# PGTN_daisy1_main_8cvin_2cvout.net
KiCad netlist of a schematic drawn in EAGLE
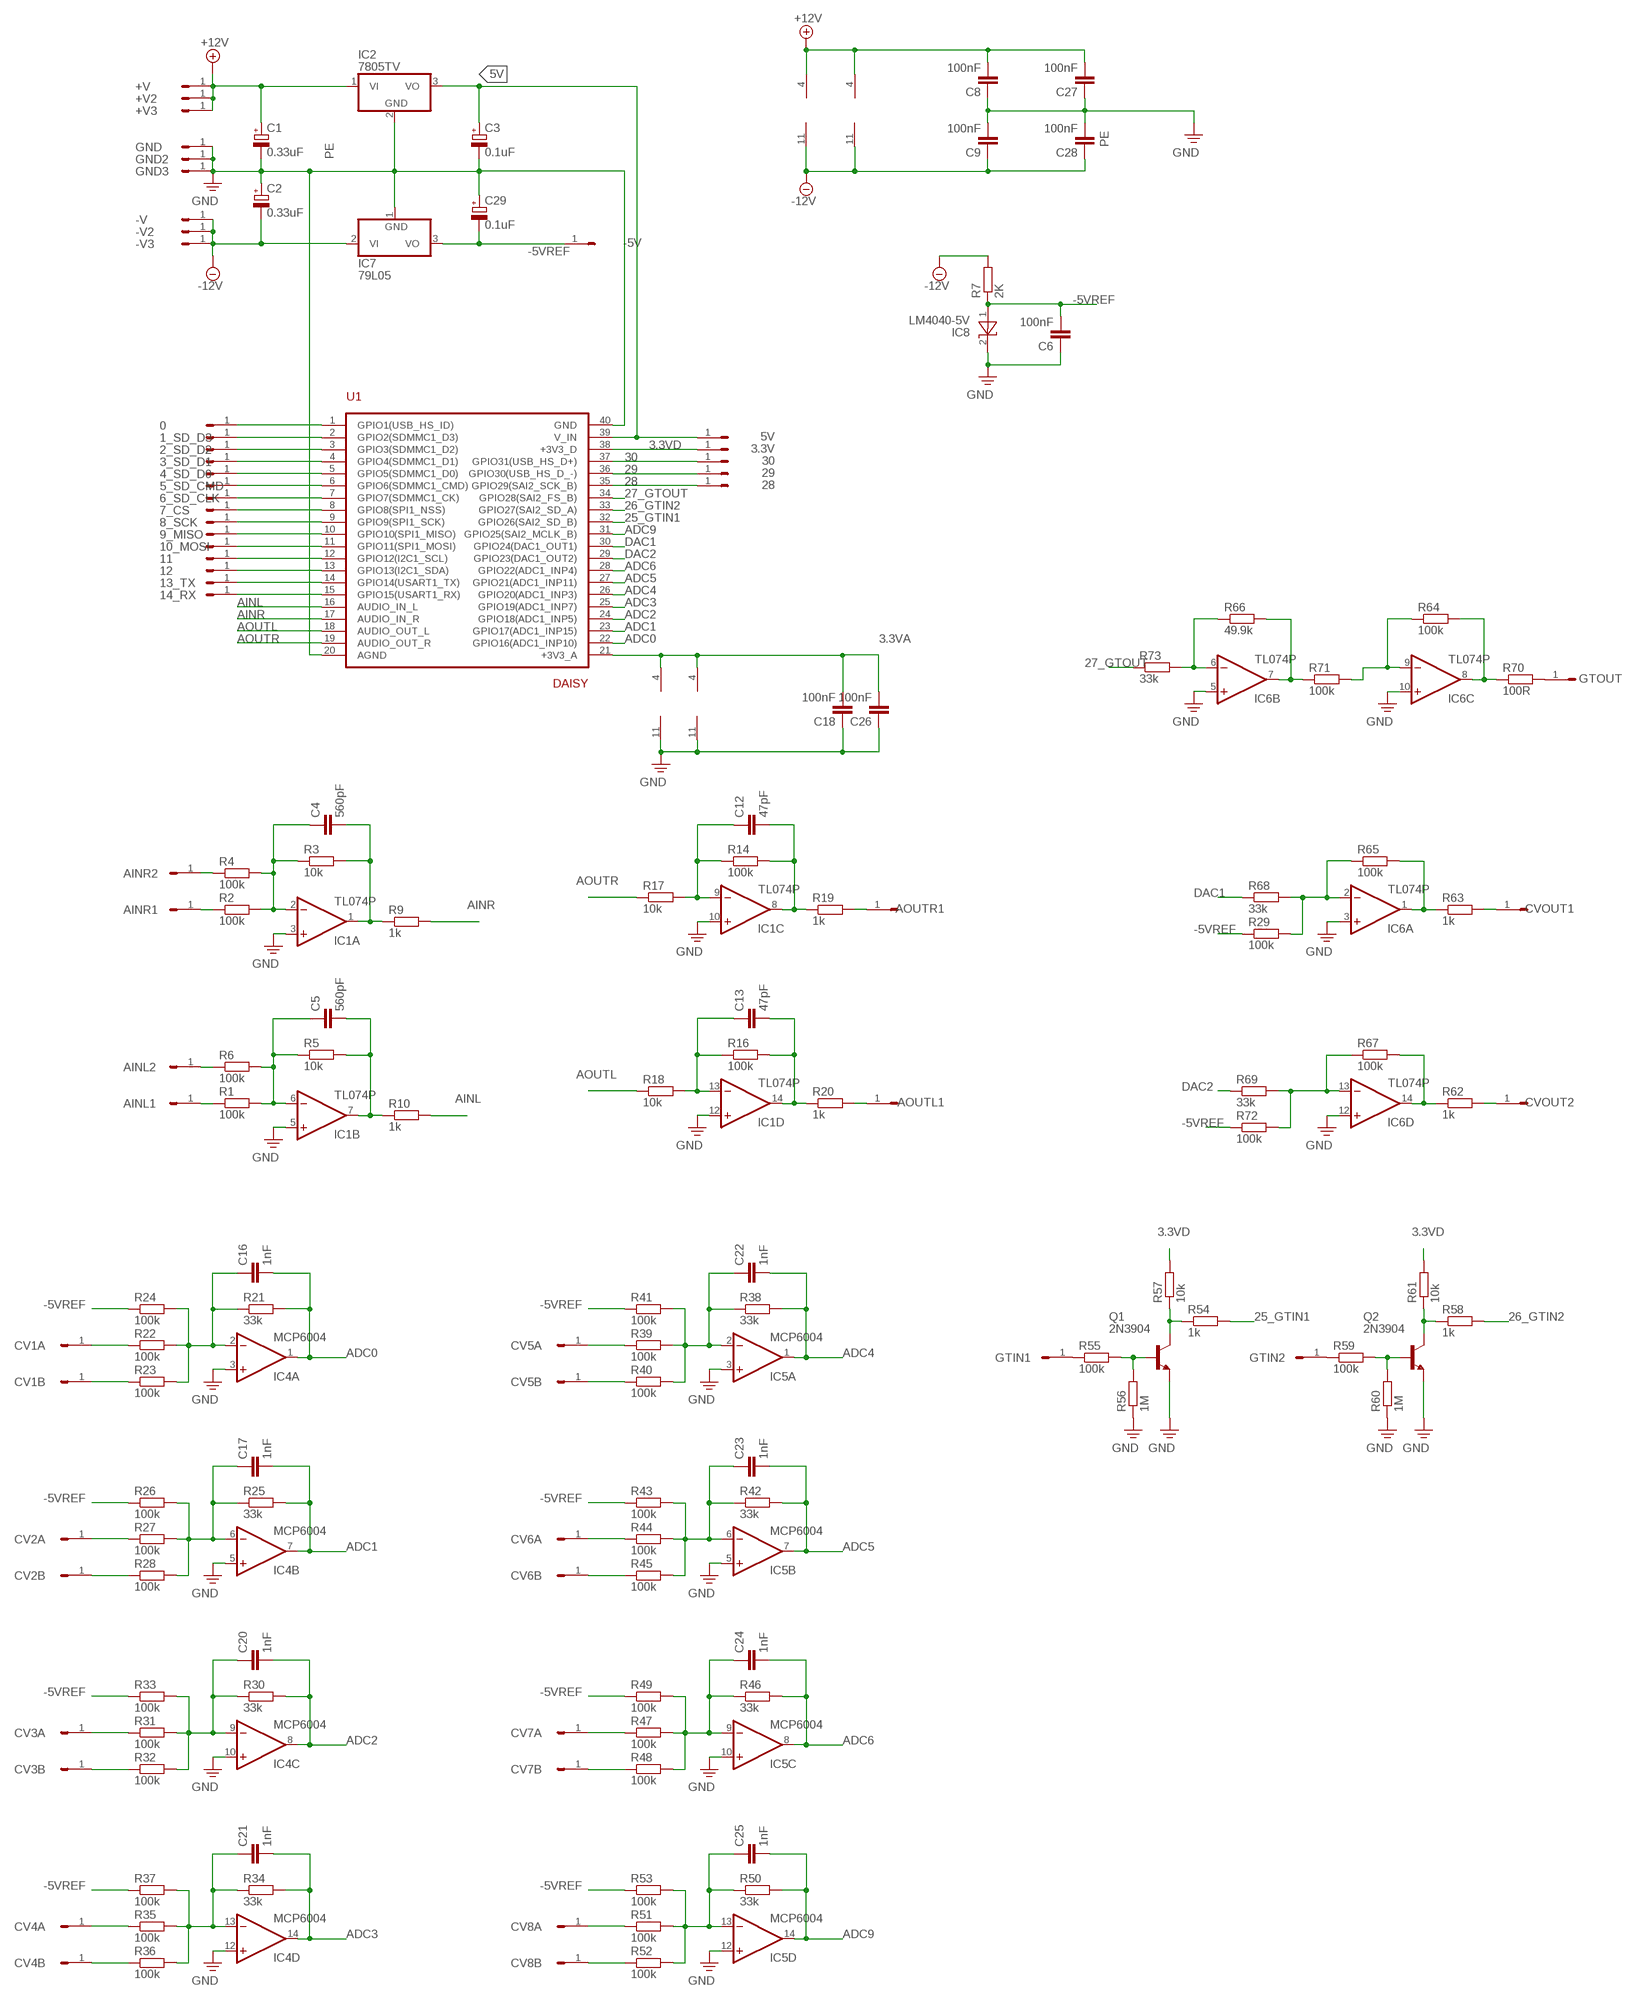
[diagram p0: schematic, sheet 1]

(export (version "E")
  (design (tool "Eeschema 10.0.6"))
  (components
    (comp (ref "+V")
      (value "HEADER/MALE/01")
      (footprint "eagle-import:HEADER_MALE_01")
      (fields (field (name "SPICEPREFIX") "X"))
      (libsource (lib "eagle-import") (part "HEADER/MALE/01"))
    )
    (comp (ref "+V2")
      (value "HEADER/MALE/01")
      (footprint "eagle-import:HEADER_MALE_01")
      (fields (field (name "SPICEPREFIX") "X"))
      (libsource (lib "eagle-import") (part "HEADER/MALE/01"))
    )
    (comp (ref "+V3")
      (value "HEADER/MALE/01")
      (footprint "eagle-import:HEADER_MALE_01")
      (fields (field (name "SPICEPREFIX") "X"))
      (libsource (lib "eagle-import") (part "HEADER/MALE/01"))
    )
    (comp (ref "-5V")
      (value "HEADER/MALE/01")
      (footprint "eagle-import:HEADER_MALE_01")
      (fields (field (name "SPICEPREFIX") "X"))
      (libsource (lib "eagle-import") (part "HEADER/MALE/01"))
    )
    (comp (ref "-V")
      (value "HEADER/MALE/01")
      (footprint "eagle-import:HEADER_MALE_01")
      (fields (field (name "SPICEPREFIX") "X"))
      (libsource (lib "eagle-import") (part "HEADER/MALE/01"))
    )
    (comp (ref "-V2")
      (value "HEADER/MALE/01")
      (footprint "eagle-import:HEADER_MALE_01")
      (fields (field (name "SPICEPREFIX") "X"))
      (libsource (lib "eagle-import") (part "HEADER/MALE/01"))
    )
    (comp (ref "-V3")
      (value "HEADER/MALE/01")
      (footprint "eagle-import:HEADER_MALE_01")
      (fields (field (name "SPICEPREFIX") "X"))
      (libsource (lib "eagle-import") (part "HEADER/MALE/01"))
    )
    (comp (ref "0")
      (value "HEADER/MALE/01")
      (footprint "eagle-import:HEADER_MALE_01")
      (fields (field (name "SPICEPREFIX") "X"))
      (libsource (lib "eagle-import") (part "HEADER/MALE/01"))
    )
    (comp (ref "1_SD_D3")
      (value "HEADER/MALE/01")
      (footprint "eagle-import:HEADER_MALE_01")
      (fields (field (name "SPICEPREFIX") "X"))
      (libsource (lib "eagle-import") (part "HEADER/MALE/01"))
    )
    (comp (ref "2_SD_D2")
      (value "HEADER/MALE/01")
      (footprint "eagle-import:HEADER_MALE_01")
      (fields (field (name "SPICEPREFIX") "X"))
      (libsource (lib "eagle-import") (part "HEADER/MALE/01"))
    )
    (comp (ref "3.3V")
      (value "HEADER/MALE/01")
      (footprint "eagle-import:HEADER_MALE_01")
      (fields (field (name "SPICEPREFIX") "X"))
      (libsource (lib "eagle-import") (part "HEADER/MALE/01"))
    )
    (comp (ref "3_SD_D1")
      (value "HEADER/MALE/01")
      (footprint "eagle-import:HEADER_MALE_01")
      (fields (field (name "SPICEPREFIX") "X"))
      (libsource (lib "eagle-import") (part "HEADER/MALE/01"))
    )
    (comp (ref "4_SD_D0")
      (value "HEADER/MALE/01")
      (footprint "eagle-import:HEADER_MALE_01")
      (fields (field (name "SPICEPREFIX") "X"))
      (libsource (lib "eagle-import") (part "HEADER/MALE/01"))
    )
    (comp (ref "5V")
      (value "HEADER/MALE/01")
      (footprint "eagle-import:HEADER_MALE_01")
      (fields (field (name "SPICEPREFIX") "X"))
      (libsource (lib "eagle-import") (part "HEADER/MALE/01"))
    )
    (comp (ref "5_SD_CMD")
      (value "HEADER/MALE/01")
      (footprint "eagle-import:HEADER_MALE_01")
      (fields (field (name "SPICEPREFIX") "X"))
      (libsource (lib "eagle-import") (part "HEADER/MALE/01"))
    )
    (comp (ref "6_SD_CLK")
      (value "HEADER/MALE/01")
      (footprint "eagle-import:HEADER_MALE_01")
      (fields (field (name "SPICEPREFIX") "X"))
      (libsource (lib "eagle-import") (part "HEADER/MALE/01"))
    )
    (comp (ref "7_CS")
      (value "HEADER/MALE/01")
      (footprint "eagle-import:HEADER_MALE_01")
      (fields (field (name "SPICEPREFIX") "X"))
      (libsource (lib "eagle-import") (part "HEADER/MALE/01"))
    )
    (comp (ref "8_SCK")
      (value "HEADER/MALE/01")
      (footprint "eagle-import:HEADER_MALE_01")
      (fields (field (name "SPICEPREFIX") "X"))
      (libsource (lib "eagle-import") (part "HEADER/MALE/01"))
    )
    (comp (ref "9_MISO")
      (value "HEADER/MALE/01")
      (footprint "eagle-import:HEADER_MALE_01")
      (fields (field (name "SPICEPREFIX") "X"))
      (libsource (lib "eagle-import") (part "HEADER/MALE/01"))
    )
    (comp (ref "10_MOSI")
      (value "HEADER/MALE/01")
      (footprint "eagle-import:HEADER_MALE_01")
      (fields (field (name "SPICEPREFIX") "X"))
      (libsource (lib "eagle-import") (part "HEADER/MALE/01"))
    )
    (comp (ref "11")
      (value "HEADER/MALE/01")
      (footprint "eagle-import:HEADER_MALE_01")
      (fields (field (name "SPICEPREFIX") "X"))
      (libsource (lib "eagle-import") (part "HEADER/MALE/01"))
    )
    (comp (ref "12")
      (value "HEADER/MALE/01")
      (footprint "eagle-import:HEADER_MALE_01")
      (fields (field (name "SPICEPREFIX") "X"))
      (libsource (lib "eagle-import") (part "HEADER/MALE/01"))
    )
    (comp (ref "13_TX")
      (value "HEADER/MALE/01")
      (footprint "eagle-import:HEADER_MALE_01")
      (fields (field (name "SPICEPREFIX") "X"))
      (libsource (lib "eagle-import") (part "HEADER/MALE/01"))
    )
    (comp (ref "14_RX")
      (value "HEADER/MALE/01")
      (footprint "eagle-import:HEADER_MALE_01")
      (fields (field (name "SPICEPREFIX") "X"))
      (libsource (lib "eagle-import") (part "HEADER/MALE/01"))
    )
    (comp (ref "28")
      (value "HEADER/MALE/01")
      (footprint "eagle-import:HEADER_MALE_01")
      (fields (field (name "SPICEPREFIX") "X"))
      (libsource (lib "eagle-import") (part "HEADER/MALE/01"))
    )
    (comp (ref "29")
      (value "HEADER/MALE/01")
      (footprint "eagle-import:HEADER_MALE_01")
      (fields (field (name "SPICEPREFIX") "X"))
      (libsource (lib "eagle-import") (part "HEADER/MALE/01"))
    )
    (comp (ref "30")
      (value "HEADER/MALE/01")
      (footprint "eagle-import:HEADER_MALE_01")
      (fields (field (name "SPICEPREFIX") "X"))
      (libsource (lib "eagle-import") (part "HEADER/MALE/01"))
    )
    (comp (ref "AINL1")
      (value "HEADER/MALE/01")
      (footprint "eagle-import:HEADER_MALE_01")
      (fields (field (name "SPICEPREFIX") "X"))
      (libsource (lib "eagle-import") (part "HEADER/MALE/01"))
    )
    (comp (ref "AINL2")
      (value "HEADER/MALE/01")
      (footprint "eagle-import:HEADER_MALE_01")
      (fields (field (name "SPICEPREFIX") "X"))
      (libsource (lib "eagle-import") (part "HEADER/MALE/01"))
    )
    (comp (ref "AINR1")
      (value "HEADER/MALE/01")
      (footprint "eagle-import:HEADER_MALE_01")
      (fields (field (name "SPICEPREFIX") "X"))
      (libsource (lib "eagle-import") (part "HEADER/MALE/01"))
    )
    (comp (ref "AINR2")
      (value "HEADER/MALE/01")
      (footprint "eagle-import:HEADER_MALE_01")
      (fields (field (name "SPICEPREFIX") "X"))
      (libsource (lib "eagle-import") (part "HEADER/MALE/01"))
    )
    (comp (ref "AOUTL1")
      (value "HEADER/MALE/01")
      (footprint "eagle-import:HEADER_MALE_01")
      (fields (field (name "SPICEPREFIX") "X"))
      (libsource (lib "eagle-import") (part "HEADER/MALE/01"))
    )
    (comp (ref "AOUTR1")
      (value "HEADER/MALE/01")
      (footprint "eagle-import:HEADER_MALE_01")
      (fields (field (name "SPICEPREFIX") "X"))
      (libsource (lib "eagle-import") (part "HEADER/MALE/01"))
    )
    (comp (ref "C1")
      (value "0.33uF")
      (footprint "eagle-import:E2,5-6")
      (fields (field (name "SPICEPREFIX") "C"))
      (libsource (lib "eagle-import") (part "CAPACITOR/POLARIZEDE2.5-6"))
    )
    (comp (ref "C2")
      (value "0.33uF")
      (footprint "eagle-import:E2,5-6")
      (fields (field (name "SPICEPREFIX") "C"))
      (libsource (lib "eagle-import") (part "CAPACITOR/POLARIZEDE2.5-6"))
    )
    (comp (ref "C3")
      (value "0.1uF")
      (footprint "eagle-import:E2,5-6")
      (fields (field (name "SPICEPREFIX") "C"))
      (libsource (lib "eagle-import") (part "CAPACITOR/POLARIZEDE2.5-6"))
    )
    (comp (ref "C4")
      (value "560pF")
      (footprint "eagle-import:CERAMICDISC_5")
      (libsource (lib "eagle-import") (part "CAPACITORCERAMICDISC/5"))
    )
    (comp (ref "C5")
      (value "560pF")
      (footprint "eagle-import:CERAMICDISC_5")
      (libsource (lib "eagle-import") (part "CAPACITORCERAMICDISC/5"))
    )
    (comp (ref "C6")
      (value "100nF")
      (footprint "eagle-import:CERAMICDISC_5")
      (libsource (lib "eagle-import") (part "CAPACITORCERAMICDISC/5"))
    )
    (comp (ref "C8")
      (value "100nF")
      (footprint "eagle-import:CERAMICDISC_5")
      (libsource (lib "eagle-import") (part "CAPACITORCERAMICDISC/5"))
    )
    (comp (ref "C9")
      (value "100nF")
      (footprint "eagle-import:CERAMICDISC_5")
      (libsource (lib "eagle-import") (part "CAPACITORCERAMICDISC/5"))
    )
    (comp (ref "C12")
      (value "47pF")
      (footprint "eagle-import:CERAMICDISC_5")
      (libsource (lib "eagle-import") (part "CAPACITORCERAMICDISC/5"))
    )
    (comp (ref "C13")
      (value "47pF")
      (footprint "eagle-import:CERAMICDISC_5")
      (libsource (lib "eagle-import") (part "CAPACITORCERAMICDISC/5"))
    )
    (comp (ref "C16")
      (value "1nF")
      (footprint "eagle-import:CERAMICDISC_5")
      (libsource (lib "eagle-import") (part "CAPACITORCERAMICDISC/5"))
    )
    (comp (ref "C17")
      (value "1nF")
      (footprint "eagle-import:CERAMICDISC_5")
      (libsource (lib "eagle-import") (part "CAPACITORCERAMICDISC/5"))
    )
    (comp (ref "C18")
      (value "100nF")
      (footprint "eagle-import:CERAMICDISC_5")
      (libsource (lib "eagle-import") (part "CAPACITORCERAMICDISC/5"))
    )
    (comp (ref "C20")
      (value "1nF")
      (footprint "eagle-import:CERAMICDISC_5")
      (libsource (lib "eagle-import") (part "CAPACITORCERAMICDISC/5"))
    )
    (comp (ref "C21")
      (value "1nF")
      (footprint "eagle-import:CERAMICDISC_5")
      (libsource (lib "eagle-import") (part "CAPACITORCERAMICDISC/5"))
    )
    (comp (ref "C22")
      (value "1nF")
      (footprint "eagle-import:CERAMICDISC_5")
      (libsource (lib "eagle-import") (part "CAPACITORCERAMICDISC/5"))
    )
    (comp (ref "C23")
      (value "1nF")
      (footprint "eagle-import:CERAMICDISC_5")
      (libsource (lib "eagle-import") (part "CAPACITORCERAMICDISC/5"))
    )
    (comp (ref "C24")
      (value "1nF")
      (footprint "eagle-import:CERAMICDISC_5")
      (libsource (lib "eagle-import") (part "CAPACITORCERAMICDISC/5"))
    )
    (comp (ref "C25")
      (value "1nF")
      (footprint "eagle-import:CERAMICDISC_5")
      (libsource (lib "eagle-import") (part "CAPACITORCERAMICDISC/5"))
    )
    (comp (ref "C26")
      (value "100nF")
      (footprint "eagle-import:CERAMICDISC_5")
      (libsource (lib "eagle-import") (part "CAPACITORCERAMICDISC/5"))
    )
    (comp (ref "C27")
      (value "100nF")
      (footprint "eagle-import:CERAMICDISC_5")
      (libsource (lib "eagle-import") (part "CAPACITORCERAMICDISC/5"))
    )
    (comp (ref "C28")
      (value "100nF")
      (footprint "eagle-import:CERAMICDISC_5")
      (libsource (lib "eagle-import") (part "CAPACITORCERAMICDISC/5"))
    )
    (comp (ref "C29")
      (value "0.1uF")
      (footprint "eagle-import:E2,5-6")
      (fields (field (name "SPICEPREFIX") "C"))
      (libsource (lib "eagle-import") (part "CAPACITOR/POLARIZEDE2.5-6"))
    )
    (comp (ref "CV1A")
      (value "HEADER/MALE/01")
      (footprint "eagle-import:HEADER_MALE_01")
      (fields (field (name "SPICEPREFIX") "X"))
      (libsource (lib "eagle-import") (part "HEADER/MALE/01"))
    )
    (comp (ref "CV1B")
      (value "HEADER/MALE/01")
      (footprint "eagle-import:HEADER_MALE_01")
      (fields (field (name "SPICEPREFIX") "X"))
      (libsource (lib "eagle-import") (part "HEADER/MALE/01"))
    )
    (comp (ref "CV2A")
      (value "HEADER/MALE/01")
      (footprint "eagle-import:HEADER_MALE_01")
      (fields (field (name "SPICEPREFIX") "X"))
      (libsource (lib "eagle-import") (part "HEADER/MALE/01"))
    )
    (comp (ref "CV2B")
      (value "HEADER/MALE/01")
      (footprint "eagle-import:HEADER_MALE_01")
      (fields (field (name "SPICEPREFIX") "X"))
      (libsource (lib "eagle-import") (part "HEADER/MALE/01"))
    )
    (comp (ref "CV3A")
      (value "HEADER/MALE/01")
      (footprint "eagle-import:HEADER_MALE_01")
      (fields (field (name "SPICEPREFIX") "X"))
      (libsource (lib "eagle-import") (part "HEADER/MALE/01"))
    )
    (comp (ref "CV3B")
      (value "HEADER/MALE/01")
      (footprint "eagle-import:HEADER_MALE_01")
      (fields (field (name "SPICEPREFIX") "X"))
      (libsource (lib "eagle-import") (part "HEADER/MALE/01"))
    )
    (comp (ref "CV4A")
      (value "HEADER/MALE/01")
      (footprint "eagle-import:HEADER_MALE_01")
      (fields (field (name "SPICEPREFIX") "X"))
      (libsource (lib "eagle-import") (part "HEADER/MALE/01"))
    )
    (comp (ref "CV4B")
      (value "HEADER/MALE/01")
      (footprint "eagle-import:HEADER_MALE_01")
      (fields (field (name "SPICEPREFIX") "X"))
      (libsource (lib "eagle-import") (part "HEADER/MALE/01"))
    )
    (comp (ref "CV5A")
      (value "HEADER/MALE/01")
      (footprint "eagle-import:HEADER_MALE_01")
      (fields (field (name "SPICEPREFIX") "X"))
      (libsource (lib "eagle-import") (part "HEADER/MALE/01"))
    )
    (comp (ref "CV5B")
      (value "HEADER/MALE/01")
      (footprint "eagle-import:HEADER_MALE_01")
      (fields (field (name "SPICEPREFIX") "X"))
      (libsource (lib "eagle-import") (part "HEADER/MALE/01"))
    )
    (comp (ref "CV6A")
      (value "HEADER/MALE/01")
      (footprint "eagle-import:HEADER_MALE_01")
      (fields (field (name "SPICEPREFIX") "X"))
      (libsource (lib "eagle-import") (part "HEADER/MALE/01"))
    )
    (comp (ref "CV6B")
      (value "HEADER/MALE/01")
      (footprint "eagle-import:HEADER_MALE_01")
      (fields (field (name "SPICEPREFIX") "X"))
      (libsource (lib "eagle-import") (part "HEADER/MALE/01"))
    )
    (comp (ref "CV7A")
      (value "HEADER/MALE/01")
      (footprint "eagle-import:HEADER_MALE_01")
      (fields (field (name "SPICEPREFIX") "X"))
      (libsource (lib "eagle-import") (part "HEADER/MALE/01"))
    )
    (comp (ref "CV7B")
      (value "HEADER/MALE/01")
      (footprint "eagle-import:HEADER_MALE_01")
      (fields (field (name "SPICEPREFIX") "X"))
      (libsource (lib "eagle-import") (part "HEADER/MALE/01"))
    )
    (comp (ref "CV8A")
      (value "HEADER/MALE/01")
      (footprint "eagle-import:HEADER_MALE_01")
      (fields (field (name "SPICEPREFIX") "X"))
      (libsource (lib "eagle-import") (part "HEADER/MALE/01"))
    )
    (comp (ref "CV8B")
      (value "HEADER/MALE/01")
      (footprint "eagle-import:HEADER_MALE_01")
      (fields (field (name "SPICEPREFIX") "X"))
      (libsource (lib "eagle-import") (part "HEADER/MALE/01"))
    )
    (comp (ref "CVOUT1")
      (value "HEADER/MALE/01")
      (footprint "eagle-import:HEADER_MALE_01")
      (fields (field (name "SPICEPREFIX") "X"))
      (libsource (lib "eagle-import") (part "HEADER/MALE/01"))
    )
    (comp (ref "CVOUT2")
      (value "HEADER/MALE/01")
      (footprint "eagle-import:HEADER_MALE_01")
      (fields (field (name "SPICEPREFIX") "X"))
      (libsource (lib "eagle-import") (part "HEADER/MALE/01"))
    )
    (comp (ref "GND")
      (value "HEADER/MALE/01")
      (footprint "eagle-import:HEADER_MALE_01")
      (fields (field (name "SPICEPREFIX") "X"))
      (libsource (lib "eagle-import") (part "HEADER/MALE/01"))
    )
    (comp (ref "GND2")
      (value "HEADER/MALE/01")
      (footprint "eagle-import:HEADER_MALE_01")
      (fields (field (name "SPICEPREFIX") "X"))
      (libsource (lib "eagle-import") (part "HEADER/MALE/01"))
    )
    (comp (ref "GND3")
      (value "HEADER/MALE/01")
      (footprint "eagle-import:HEADER_MALE_01")
      (fields (field (name "SPICEPREFIX") "X"))
      (libsource (lib "eagle-import") (part "HEADER/MALE/01"))
    )
    (comp (ref "GTIN1")
      (value "HEADER/MALE/01")
      (footprint "eagle-import:HEADER_MALE_01")
      (fields (field (name "SPICEPREFIX") "X"))
      (libsource (lib "eagle-import") (part "HEADER/MALE/01"))
    )
    (comp (ref "GTIN2")
      (value "HEADER/MALE/01")
      (footprint "eagle-import:HEADER_MALE_01")
      (fields (field (name "SPICEPREFIX") "X"))
      (libsource (lib "eagle-import") (part "HEADER/MALE/01"))
    )
    (comp (ref "GTOUT")
      (value "HEADER/MALE/01")
      (footprint "eagle-import:HEADER_MALE_01")
      (fields (field (name "SPICEPREFIX") "X"))
      (libsource (lib "eagle-import") (part "HEADER/MALE/01"))
    )
    (comp (ref "IC1")
      (value "TL074P")
      (footprint "eagle-import:DIL14")
      (libsource (lib "eagle-import") (part "TL074P"))
    )
    (comp (ref "IC2")
      (value "7805TV")
      (footprint "eagle-import:TO220V")
      (libsource (lib "eagle-import") (part "78TV05"))
    )
    (comp (ref "IC4")
      (value "MCP6004")
      (footprint "eagle-import:DIL14")
      (libsource (lib "eagle-import") (part "TL074P"))
    )
    (comp (ref "IC5")
      (value "MCP6004")
      (footprint "eagle-import:DIL14")
      (libsource (lib "eagle-import") (part "TL074P"))
    )
    (comp (ref "IC6")
      (value "TL074P")
      (footprint "eagle-import:DIL14")
      (libsource (lib "eagle-import") (part "TL074P"))
    )
    (comp (ref "IC7")
      (value "79L05")
      (footprint "eagle-import:TO92")
      (libsource (lib "eagle-import") (part "79ZL05"))
    )
    (comp (ref "IC8")
      (value "LM4040-5V")
      (footprint "eagle-import:TO92")
      (libsource (lib "eagle-import") (part "LM4040"))
    )
    (comp (ref "Q1")
      (value "2N3904")
      (footprint "eagle-import:TO92")
      (libsource (lib "eagle-import") (part "2N3904"))
    )
    (comp (ref "Q2")
      (value "2N3904")
      (footprint "eagle-import:TO92")
      (libsource (lib "eagle-import") (part "2N3904"))
    )
    (comp (ref "R1")
      (value "100k")
      (footprint "eagle-import:RESISTOR_7.5")
      (libsource (lib "eagle-import") (part "RESISTORRESISTOR/UPRIGHT/7.5"))
    )
    (comp (ref "R2")
      (value "100k")
      (footprint "eagle-import:RESISTOR_7.5")
      (libsource (lib "eagle-import") (part "RESISTORRESISTOR/UPRIGHT/7.5"))
    )
    (comp (ref "R3")
      (value "10k")
      (footprint "eagle-import:RESISTOR_7.5")
      (libsource (lib "eagle-import") (part "RESISTORRESISTOR/UPRIGHT/7.5"))
    )
    (comp (ref "R4")
      (value "100k")
      (footprint "eagle-import:RESISTOR_7.5")
      (libsource (lib "eagle-import") (part "RESISTORRESISTOR/UPRIGHT/7.5"))
    )
    (comp (ref "R5")
      (value "10k")
      (footprint "eagle-import:RESISTOR_7.5")
      (libsource (lib "eagle-import") (part "RESISTORRESISTOR/UPRIGHT/7.5"))
    )
    (comp (ref "R6")
      (value "100k")
      (footprint "eagle-import:RESISTOR_7.5")
      (libsource (lib "eagle-import") (part "RESISTORRESISTOR/UPRIGHT/7.5"))
    )
    (comp (ref "R7")
      (value "2K")
      (footprint "eagle-import:RESISTOR_7.5")
      (libsource (lib "eagle-import") (part "RESISTORRESISTOR/UPRIGHT/7.5"))
    )
    (comp (ref "R9")
      (value "1k")
      (footprint "eagle-import:RESISTOR_7.5")
      (libsource (lib "eagle-import") (part "RESISTORRESISTOR/UPRIGHT/7.5"))
    )
    (comp (ref "R10")
      (value "1k")
      (footprint "eagle-import:RESISTOR_7.5")
      (libsource (lib "eagle-import") (part "RESISTORRESISTOR/UPRIGHT/7.5"))
    )
    (comp (ref "R14")
      (value "100k")
      (footprint "eagle-import:RESISTOR_7.5")
      (libsource (lib "eagle-import") (part "RESISTORRESISTOR/UPRIGHT/7.5"))
    )
    (comp (ref "R16")
      (value "100k")
      (footprint "eagle-import:RESISTOR_7.5")
      (libsource (lib "eagle-import") (part "RESISTORRESISTOR/UPRIGHT/7.5"))
    )
    (comp (ref "R17")
      (value "10k")
      (footprint "eagle-import:RESISTOR_7.5")
      (libsource (lib "eagle-import") (part "RESISTORRESISTOR/UPRIGHT/7.5"))
    )
    (comp (ref "R18")
      (value "10k")
      (footprint "eagle-import:RESISTOR_7.5")
      (libsource (lib "eagle-import") (part "RESISTORRESISTOR/UPRIGHT/7.5"))
    )
    (comp (ref "R19")
      (value "1k")
      (footprint "eagle-import:RESISTOR_7.5")
      (libsource (lib "eagle-import") (part "RESISTORRESISTOR/UPRIGHT/7.5"))
    )
    (comp (ref "R20")
      (value "1k")
      (footprint "eagle-import:RESISTOR_7.5")
      (libsource (lib "eagle-import") (part "RESISTORRESISTOR/UPRIGHT/7.5"))
    )
    (comp (ref "R21")
      (value "33k")
      (footprint "eagle-import:RESISTOR_7.5")
      (libsource (lib "eagle-import") (part "RESISTORRESISTOR/UPRIGHT/7.5"))
    )
    (comp (ref "R22")
      (value "100k")
      (footprint "eagle-import:RESISTOR_7.5")
      (libsource (lib "eagle-import") (part "RESISTORRESISTOR/UPRIGHT/7.5"))
    )
    (comp (ref "R23")
      (value "100k")
      (footprint "eagle-import:RESISTOR_7.5")
      (libsource (lib "eagle-import") (part "RESISTORRESISTOR/UPRIGHT/7.5"))
    )
    (comp (ref "R24")
      (value "100k")
      (footprint "eagle-import:RESISTOR_7.5")
      (libsource (lib "eagle-import") (part "RESISTORRESISTOR/UPRIGHT/7.5"))
    )
    (comp (ref "R25")
      (value "33k")
      (footprint "eagle-import:RESISTOR_7.5")
      (libsource (lib "eagle-import") (part "RESISTORRESISTOR/UPRIGHT/7.5"))
    )
    (comp (ref "R26")
      (value "100k")
      (footprint "eagle-import:RESISTOR_7.5")
      (libsource (lib "eagle-import") (part "RESISTORRESISTOR/UPRIGHT/7.5"))
    )
    (comp (ref "R27")
      (value "100k")
      (footprint "eagle-import:RESISTOR_7.5")
      (libsource (lib "eagle-import") (part "RESISTORRESISTOR/UPRIGHT/7.5"))
    )
    (comp (ref "R28")
      (value "100k")
      (footprint "eagle-import:RESISTOR_7.5")
      (libsource (lib "eagle-import") (part "RESISTORRESISTOR/UPRIGHT/7.5"))
    )
    (comp (ref "R29")
      (value "100k")
      (footprint "eagle-import:RESISTOR_7.5")
      (libsource (lib "eagle-import") (part "RESISTORRESISTOR/UPRIGHT/7.5"))
    )
    (comp (ref "R30")
      (value "33k")
      (footprint "eagle-import:RESISTOR_7.5")
      (libsource (lib "eagle-import") (part "RESISTORRESISTOR/UPRIGHT/7.5"))
    )
    (comp (ref "R31")
      (value "100k")
      (footprint "eagle-import:RESISTOR_7.5")
      (libsource (lib "eagle-import") (part "RESISTORRESISTOR/UPRIGHT/7.5"))
    )
    (comp (ref "R32")
      (value "100k")
      (footprint "eagle-import:RESISTOR_7.5")
      (libsource (lib "eagle-import") (part "RESISTORRESISTOR/UPRIGHT/7.5"))
    )
    (comp (ref "R33")
      (value "100k")
      (footprint "eagle-import:RESISTOR_7.5")
      (libsource (lib "eagle-import") (part "RESISTORRESISTOR/UPRIGHT/7.5"))
    )
    (comp (ref "R34")
      (value "33k")
      (footprint "eagle-import:RESISTOR_7.5")
      (libsource (lib "eagle-import") (part "RESISTORRESISTOR/UPRIGHT/7.5"))
    )
    (comp (ref "R35")
      (value "100k")
      (footprint "eagle-import:RESISTOR_7.5")
      (libsource (lib "eagle-import") (part "RESISTORRESISTOR/UPRIGHT/7.5"))
    )
    (comp (ref "R36")
      (value "100k")
      (footprint "eagle-import:RESISTOR_7.5")
      (libsource (lib "eagle-import") (part "RESISTORRESISTOR/UPRIGHT/7.5"))
    )
    (comp (ref "R37")
      (value "100k")
      (footprint "eagle-import:RESISTOR_7.5")
      (libsource (lib "eagle-import") (part "RESISTORRESISTOR/UPRIGHT/7.5"))
    )
    (comp (ref "R38")
      (value "33k")
      (footprint "eagle-import:RESISTOR_7.5")
      (libsource (lib "eagle-import") (part "RESISTORRESISTOR/UPRIGHT/7.5"))
    )
    (comp (ref "R39")
      (value "100k")
      (footprint "eagle-import:RESISTOR_7.5")
      (libsource (lib "eagle-import") (part "RESISTORRESISTOR/UPRIGHT/7.5"))
    )
    (comp (ref "R40")
      (value "100k")
      (footprint "eagle-import:RESISTOR_7.5")
      (libsource (lib "eagle-import") (part "RESISTORRESISTOR/UPRIGHT/7.5"))
    )
    (comp (ref "R41")
      (value "100k")
      (footprint "eagle-import:RESISTOR_7.5")
      (libsource (lib "eagle-import") (part "RESISTORRESISTOR/UPRIGHT/7.5"))
    )
    (comp (ref "R42")
      (value "33k")
      (footprint "eagle-import:RESISTOR_7.5")
      (libsource (lib "eagle-import") (part "RESISTORRESISTOR/UPRIGHT/7.5"))
    )
    (comp (ref "R43")
      (value "100k")
      (footprint "eagle-import:RESISTOR_7.5")
      (libsource (lib "eagle-import") (part "RESISTORRESISTOR/UPRIGHT/7.5"))
    )
    (comp (ref "R44")
      (value "100k")
      (footprint "eagle-import:RESISTOR_7.5")
      (libsource (lib "eagle-import") (part "RESISTORRESISTOR/UPRIGHT/7.5"))
    )
    (comp (ref "R45")
      (value "100k")
      (footprint "eagle-import:RESISTOR_7.5")
      (libsource (lib "eagle-import") (part "RESISTORRESISTOR/UPRIGHT/7.5"))
    )
    (comp (ref "R46")
      (value "33k")
      (footprint "eagle-import:RESISTOR_7.5")
      (libsource (lib "eagle-import") (part "RESISTORRESISTOR/UPRIGHT/7.5"))
    )
    (comp (ref "R47")
      (value "100k")
      (footprint "eagle-import:RESISTOR_7.5")
      (libsource (lib "eagle-import") (part "RESISTORRESISTOR/UPRIGHT/7.5"))
    )
    (comp (ref "R48")
      (value "100k")
      (footprint "eagle-import:RESISTOR_7.5")
      (libsource (lib "eagle-import") (part "RESISTORRESISTOR/UPRIGHT/7.5"))
    )
    (comp (ref "R49")
      (value "100k")
      (footprint "eagle-import:RESISTOR_7.5")
      (libsource (lib "eagle-import") (part "RESISTORRESISTOR/UPRIGHT/7.5"))
    )
    (comp (ref "R50")
      (value "33k")
      (footprint "eagle-import:RESISTOR_7.5")
      (libsource (lib "eagle-import") (part "RESISTORRESISTOR/UPRIGHT/7.5"))
    )
    (comp (ref "R51")
      (value "100k")
      (footprint "eagle-import:RESISTOR_7.5")
      (libsource (lib "eagle-import") (part "RESISTORRESISTOR/UPRIGHT/7.5"))
    )
    (comp (ref "R52")
      (value "100k")
      (footprint "eagle-import:RESISTOR_7.5")
      (libsource (lib "eagle-import") (part "RESISTORRESISTOR/UPRIGHT/7.5"))
    )
    (comp (ref "R53")
      (value "100k")
      (footprint "eagle-import:RESISTOR_7.5")
      (libsource (lib "eagle-import") (part "RESISTORRESISTOR/UPRIGHT/7.5"))
    )
    (comp (ref "R54")
      (value "1k")
      (footprint "eagle-import:RESISTOR_7.5")
      (libsource (lib "eagle-import") (part "RESISTORRESISTOR/UPRIGHT/7.5"))
    )
    (comp (ref "R55")
      (value "100k")
      (footprint "eagle-import:RESISTOR_7.5")
      (libsource (lib "eagle-import") (part "RESISTORRESISTOR/UPRIGHT/7.5"))
    )
    (comp (ref "R56")
      (value "1M")
      (footprint "eagle-import:RESISTOR_7.5")
      (libsource (lib "eagle-import") (part "RESISTORRESISTOR/UPRIGHT/7.5"))
    )
    (comp (ref "R57")
      (value "10k")
      (footprint "eagle-import:RESISTOR_7.5")
      (libsource (lib "eagle-import") (part "RESISTORRESISTOR/UPRIGHT/7.5"))
    )
    (comp (ref "R58")
      (value "1k")
      (footprint "eagle-import:RESISTOR_7.5")
      (libsource (lib "eagle-import") (part "RESISTORRESISTOR/UPRIGHT/7.5"))
    )
    (comp (ref "R59")
      (value "100k")
      (footprint "eagle-import:RESISTOR_7.5")
      (libsource (lib "eagle-import") (part "RESISTORRESISTOR/UPRIGHT/7.5"))
    )
    (comp (ref "R60")
      (value "1M")
      (footprint "eagle-import:RESISTOR_7.5")
      (libsource (lib "eagle-import") (part "RESISTORRESISTOR/UPRIGHT/7.5"))
    )
    (comp (ref "R61")
      (value "10k")
      (footprint "eagle-import:RESISTOR_7.5")
      (libsource (lib "eagle-import") (part "RESISTORRESISTOR/UPRIGHT/7.5"))
    )
    (comp (ref "R62")
      (value "1k")
      (footprint "eagle-import:RESISTOR_7.5")
      (libsource (lib "eagle-import") (part "RESISTORRESISTOR/UPRIGHT/7.5"))
    )
    (comp (ref "R63")
      (value "1k")
      (footprint "eagle-import:RESISTOR_7.5")
      (libsource (lib "eagle-import") (part "RESISTORRESISTOR/UPRIGHT/7.5"))
    )
    (comp (ref "R64")
      (value "100k")
      (footprint "eagle-import:RESISTOR_7.5")
      (libsource (lib "eagle-import") (part "RESISTORRESISTOR/UPRIGHT/7.5"))
    )
    (comp (ref "R65")
      (value "100k")
      (footprint "eagle-import:RESISTOR_7.5")
      (libsource (lib "eagle-import") (part "RESISTORRESISTOR/UPRIGHT/7.5"))
    )
    (comp (ref "R66")
      (value "49.9k")
      (footprint "eagle-import:RESISTOR_7.5")
      (libsource (lib "eagle-import") (part "RESISTORRESISTOR/UPRIGHT/7.5"))
    )
    (comp (ref "R67")
      (value "100k")
      (footprint "eagle-import:RESISTOR_7.5")
      (libsource (lib "eagle-import") (part "RESISTORRESISTOR/UPRIGHT/7.5"))
    )
    (comp (ref "R68")
      (value "33k")
      (footprint "eagle-import:RESISTOR_7.5")
      (libsource (lib "eagle-import") (part "RESISTORRESISTOR/UPRIGHT/7.5"))
    )
    (comp (ref "R69")
      (value "33k")
      (footprint "eagle-import:RESISTOR_7.5")
      (libsource (lib "eagle-import") (part "RESISTORRESISTOR/UPRIGHT/7.5"))
    )
    (comp (ref "R70")
      (value "100R")
      (footprint "eagle-import:RESISTOR_7.5")
      (libsource (lib "eagle-import") (part "RESISTORRESISTOR/UPRIGHT/7.5"))
    )
    (comp (ref "R71")
      (value "100k")
      (footprint "eagle-import:RESISTOR_7.5")
      (libsource (lib "eagle-import") (part "RESISTORRESISTOR/UPRIGHT/7.5"))
    )
    (comp (ref "R72")
      (value "100k")
      (footprint "eagle-import:RESISTOR_7.5")
      (libsource (lib "eagle-import") (part "RESISTORRESISTOR/UPRIGHT/7.5"))
    )
    (comp (ref "R73")
      (value "33k")
      (footprint "eagle-import:RESISTOR_7.5")
      (libsource (lib "eagle-import") (part "RESISTORRESISTOR/UPRIGHT/7.5"))
    )
    (comp (ref "U1")
      (value "DAISY")
      (footprint "eagle-import:ES_DAISY_SEED")
      (libsource (lib "eagle-import") (part "ES_DAISY_SEED_REV4"))
    )
  )
  (nets
    (net (code "1") (name "+12V") (class "Default")
      (node (ref "+V") (pin "1") (pinfunction "3_1") (pintype "passive"))
      (node (ref "+V2") (pin "1") (pinfunction "3_1") (pintype "passive"))
      (node (ref "+V3") (pin "1") (pinfunction "3_1") (pintype "passive"))
      (node (ref "C1") (pin "+") (pinfunction "+_+") (pintype "passive"))
      (node (ref "C27") (pin "2") (pinfunction "2_2") (pintype "passive"))
      (node (ref "C8") (pin "2") (pinfunction "2_2") (pintype "passive"))
      (node (ref "IC1") (pin "4") (pinfunction "V+_4") (pintype "power_in"))
      (node (ref "IC2") (pin "1") (pinfunction "VI_1") (pintype "input"))
      (node (ref "IC6") (pin "4") (pinfunction "V+_4") (pintype "power_in"))
    )
    (net (code "2") (name "-12V") (class "Default")
      (node (ref "-V") (pin "1") (pinfunction "3_1") (pintype "passive"))
      (node (ref "-V2") (pin "1") (pinfunction "3_1") (pintype "passive"))
      (node (ref "-V3") (pin "1") (pinfunction "3_1") (pintype "passive"))
      (node (ref "C2") (pin "-") (pinfunction "-_-") (pintype "passive"))
      (node (ref "C28") (pin "1") (pinfunction "1_1") (pintype "passive"))
      (node (ref "C9") (pin "1") (pinfunction "1_1") (pintype "passive"))
      (node (ref "IC1") (pin "11") (pinfunction "V-_11") (pintype "power_in"))
      (node (ref "IC6") (pin "11") (pinfunction "V-_11") (pintype "power_in"))
      (node (ref "IC7") (pin "2") (pinfunction "VI_2") (pintype "input"))
      (node (ref "R7") (pin "2") (pinfunction "2_2") (pintype "passive"))
    )
    (net (code "3") (name "/-5VREF") (class "Default")
      (node (ref "-5V") (pin "1") (pinfunction "3_1") (pintype "passive"))
      (node (ref "C29") (pin "-") (pinfunction "-_-") (pintype "passive"))
      (node (ref "C6") (pin "2") (pinfunction "2_2") (pintype "passive"))
      (node (ref "IC7") (pin "3") (pinfunction "VO_3") (pintype "passive"))
      (node (ref "IC8") (pin "1") (pinfunction "A_1") (pintype "output"))
      (node (ref "R24") (pin "1") (pinfunction "1_1") (pintype "passive"))
      (node (ref "R26") (pin "1") (pinfunction "1_1") (pintype "passive"))
      (node (ref "R29") (pin "1") (pinfunction "1_1") (pintype "passive"))
      (node (ref "R33") (pin "1") (pinfunction "1_1") (pintype "passive"))
      (node (ref "R37") (pin "1") (pinfunction "1_1") (pintype "passive"))
      (node (ref "R41") (pin "1") (pinfunction "1_1") (pintype "passive"))
      (node (ref "R43") (pin "1") (pinfunction "1_1") (pintype "passive"))
      (node (ref "R49") (pin "1") (pinfunction "1_1") (pintype "passive"))
      (node (ref "R53") (pin "1") (pinfunction "1_1") (pintype "passive"))
      (node (ref "R7") (pin "1") (pinfunction "1_1") (pintype "passive"))
      (node (ref "R72") (pin "1") (pinfunction "1_1") (pintype "passive"))
    )
    (net (code "4") (name "/3.3VA") (class "Default")
      (node (ref "C18") (pin "2") (pinfunction "2_2") (pintype "passive"))
      (node (ref "C26") (pin "2") (pinfunction "2_2") (pintype "passive"))
      (node (ref "IC4") (pin "4") (pinfunction "V+_4") (pintype "power_in"))
      (node (ref "IC5") (pin "4") (pinfunction "V+_4") (pintype "power_in"))
      (node (ref "U1") (pin "21") (pinfunction "+3V3_A_21") (pintype "bidirectional"))
    )
    (net (code "5") (name "/3.3VD") (class "Default")
      (node (ref "3.3V") (pin "1") (pinfunction "3_1") (pintype "passive"))
      (node (ref "R57") (pin "2") (pinfunction "2_2") (pintype "passive"))
      (node (ref "R61") (pin "2") (pinfunction "2_2") (pintype "passive"))
      (node (ref "U1") (pin "38") (pinfunction "+3V3_D_38") (pintype "bidirectional"))
    )
    (net (code "6") (name "/25_GTIN1") (class "Default")
      (node (ref "R54") (pin "2") (pinfunction "2_2") (pintype "passive"))
      (node (ref "U1") (pin "32") (pinfunction "GPIO26(SAI2_SD_B)_32") (pintype "bidirectional"))
    )
    (net (code "7") (name "/26_GTIN2") (class "Default")
      (node (ref "R58") (pin "2") (pinfunction "2_2") (pintype "passive"))
      (node (ref "U1") (pin "33") (pinfunction "GPIO27(SAI2_SD_A)_33") (pintype "bidirectional"))
    )
    (net (code "8") (name "/27_GTOUT") (class "Default")
      (node (ref "R73") (pin "1") (pinfunction "1_1") (pintype "passive"))
      (node (ref "U1") (pin "34") (pinfunction "GPIO28(SAI2_FS_B)_34") (pintype "bidirectional"))
    )
    (net (code "9") (name "/28") (class "Default")
      (node (ref "28") (pin "1") (pinfunction "3_1") (pintype "passive"))
      (node (ref "U1") (pin "35") (pinfunction "GPIO29(SAI2_SCK_B)_35") (pintype "bidirectional"))
    )
    (net (code "10") (name "/29") (class "Default")
      (node (ref "29") (pin "1") (pinfunction "3_1") (pintype "passive"))
      (node (ref "U1") (pin "36") (pinfunction "GPIO30(USB_HS_D_-)_36") (pintype "bidirectional"))
    )
    (net (code "11") (name "/30") (class "Default")
      (node (ref "30") (pin "1") (pinfunction "3_1") (pintype "passive"))
      (node (ref "U1") (pin "37") (pinfunction "GPIO31(USB_HS_D+)_37") (pintype "bidirectional"))
    )
    (net (code "12") (name "/ADC0") (class "Default")
      (node (ref "C16") (pin "2") (pinfunction "2_2") (pintype "passive"))
      (node (ref "IC4") (pin "1") (pinfunction "OUT_1") (pintype "output"))
      (node (ref "R21") (pin "2") (pinfunction "2_2") (pintype "passive"))
      (node (ref "U1") (pin "22") (pinfunction "GPIO16(ADC1_INP10)_22") (pintype "bidirectional"))
    )
    (net (code "13") (name "/ADC1") (class "Default")
      (node (ref "C17") (pin "2") (pinfunction "2_2") (pintype "passive"))
      (node (ref "IC4") (pin "7") (pinfunction "OUT_7") (pintype "output"))
      (node (ref "R25") (pin "2") (pinfunction "2_2") (pintype "passive"))
      (node (ref "U1") (pin "23") (pinfunction "GPIO17(ADC1_INP15)_23") (pintype "bidirectional"))
    )
    (net (code "14") (name "/ADC2") (class "Default")
      (node (ref "C20") (pin "2") (pinfunction "2_2") (pintype "passive"))
      (node (ref "IC4") (pin "8") (pinfunction "OUT_8") (pintype "output"))
      (node (ref "R30") (pin "2") (pinfunction "2_2") (pintype "passive"))
      (node (ref "U1") (pin "24") (pinfunction "GPIO18(ADC1_INP5)_24") (pintype "bidirectional"))
    )
    (net (code "15") (name "/ADC3") (class "Default")
      (node (ref "C21") (pin "2") (pinfunction "2_2") (pintype "passive"))
      (node (ref "IC4") (pin "14") (pinfunction "OUT_14") (pintype "output"))
      (node (ref "R34") (pin "2") (pinfunction "2_2") (pintype "passive"))
      (node (ref "U1") (pin "25") (pinfunction "GPIO19(ADC1_INP7)_25") (pintype "bidirectional"))
    )
    (net (code "16") (name "/ADC4") (class "Default")
      (node (ref "C22") (pin "2") (pinfunction "2_2") (pintype "passive"))
      (node (ref "IC5") (pin "1") (pinfunction "OUT_1") (pintype "output"))
      (node (ref "R38") (pin "2") (pinfunction "2_2") (pintype "passive"))
      (node (ref "U1") (pin "26") (pinfunction "GPIO20(ADC1_INP3)_26") (pintype "bidirectional"))
    )
    (net (code "17") (name "/ADC5") (class "Default")
      (node (ref "C23") (pin "2") (pinfunction "2_2") (pintype "passive"))
      (node (ref "IC5") (pin "7") (pinfunction "OUT_7") (pintype "output"))
      (node (ref "R42") (pin "2") (pinfunction "2_2") (pintype "passive"))
      (node (ref "U1") (pin "27") (pinfunction "GPIO21(ADC1_INP11)_27") (pintype "bidirectional"))
    )
    (net (code "18") (name "/ADC6") (class "Default")
      (node (ref "C24") (pin "2") (pinfunction "2_2") (pintype "passive"))
      (node (ref "IC5") (pin "8") (pinfunction "OUT_8") (pintype "output"))
      (node (ref "R46") (pin "2") (pinfunction "2_2") (pintype "passive"))
      (node (ref "U1") (pin "28") (pinfunction "GPIO22(ADC1_INP4)_28") (pintype "bidirectional"))
    )
    (net (code "19") (name "/ADC9") (class "Default")
      (node (ref "C25") (pin "2") (pinfunction "2_2") (pintype "passive"))
      (node (ref "IC5") (pin "14") (pinfunction "OUT_14") (pintype "output"))
      (node (ref "R50") (pin "2") (pinfunction "2_2") (pintype "passive"))
      (node (ref "U1") (pin "31") (pinfunction "GPIO25(SAI2_MCLK_B)_31") (pintype "bidirectional"))
    )
    (net (code "20") (name "/AINL") (class "Default")
      (node (ref "R10") (pin "2") (pinfunction "2_2") (pintype "passive"))
      (node (ref "U1") (pin "16") (pinfunction "AUDIO_IN_L_16") (pintype "bidirectional"))
    )
    (net (code "21") (name "/AINR") (class "Default")
      (node (ref "R9") (pin "2") (pinfunction "2_2") (pintype "passive"))
      (node (ref "U1") (pin "17") (pinfunction "AUDIO_IN_R_17") (pintype "bidirectional"))
    )
    (net (code "22") (name "/AOUTL") (class "Default")
      (node (ref "R18") (pin "1") (pinfunction "1_1") (pintype "passive"))
      (node (ref "U1") (pin "18") (pinfunction "AUDIO_OUT_L_18") (pintype "bidirectional"))
    )
    (net (code "23") (name "/AOUTR") (class "Default")
      (node (ref "R17") (pin "1") (pinfunction "1_1") (pintype "passive"))
      (node (ref "U1") (pin "19") (pinfunction "AUDIO_OUT_R_19") (pintype "bidirectional"))
    )
    (net (code "24") (name "/DAC1") (class "Default")
      (node (ref "R68") (pin "1") (pinfunction "1_1") (pintype "passive"))
      (node (ref "U1") (pin "30") (pinfunction "GPIO24(DAC1_OUT1)_30") (pintype "bidirectional"))
    )
    (net (code "25") (name "/DAC2") (class "Default")
      (node (ref "R69") (pin "1") (pinfunction "1_1") (pintype "passive"))
      (node (ref "U1") (pin "29") (pinfunction "GPIO23(DAC1_OUT2)_29") (pintype "bidirectional"))
    )
    (net (code "26") (name "5V") (class "Default")
      (node (ref "5V") (pin "1") (pinfunction "3_1") (pintype "passive"))
      (node (ref "C3") (pin "+") (pinfunction "+_+") (pintype "passive"))
      (node (ref "IC2") (pin "3") (pinfunction "VO_3") (pintype "passive"))
      (node (ref "U1") (pin "39") (pinfunction "V_IN_39") (pintype "bidirectional"))
    )
    (net (code "27") (name "GND") (class "Default")
      (node (ref "C1") (pin "-") (pinfunction "-_-") (pintype "passive"))
      (node (ref "C18") (pin "1") (pinfunction "1_1") (pintype "passive"))
      (node (ref "C2") (pin "+") (pinfunction "+_+") (pintype "passive"))
      (node (ref "C26") (pin "1") (pinfunction "1_1") (pintype "passive"))
      (node (ref "C27") (pin "1") (pinfunction "1_1") (pintype "passive"))
      (node (ref "C28") (pin "2") (pinfunction "2_2") (pintype "passive"))
      (node (ref "C29") (pin "+") (pinfunction "+_+") (pintype "passive"))
      (node (ref "C3") (pin "-") (pinfunction "-_-") (pintype "passive"))
      (node (ref "C6") (pin "1") (pinfunction "1_1") (pintype "passive"))
      (node (ref "C8") (pin "1") (pinfunction "1_1") (pintype "passive"))
      (node (ref "C9") (pin "2") (pinfunction "2_2") (pintype "passive"))
      (node (ref "GND") (pin "1") (pinfunction "3_1") (pintype "passive"))
      (node (ref "GND2") (pin "1") (pinfunction "3_1") (pintype "passive"))
      (node (ref "GND3") (pin "1") (pinfunction "3_1") (pintype "passive"))
      (node (ref "IC1") (pin "10") (pinfunction "+IN_10") (pintype "input"))
      (node (ref "IC1") (pin "12") (pinfunction "+IN_12") (pintype "input"))
      (node (ref "IC1") (pin "3") (pinfunction "+IN_3") (pintype "input"))
      (node (ref "IC1") (pin "5") (pinfunction "+IN_5") (pintype "input"))
      (node (ref "IC2") (pin "2") (pinfunction "GND_2") (pintype "passive"))
      (node (ref "IC4") (pin "10") (pinfunction "+IN_10") (pintype "input"))
      (node (ref "IC4") (pin "11") (pinfunction "V-_11") (pintype "power_in"))
      (node (ref "IC4") (pin "12") (pinfunction "+IN_12") (pintype "input"))
      (node (ref "IC4") (pin "3") (pinfunction "+IN_3") (pintype "input"))
      (node (ref "IC4") (pin "5") (pinfunction "+IN_5") (pintype "input"))
      (node (ref "IC5") (pin "10") (pinfunction "+IN_10") (pintype "input"))
      (node (ref "IC5") (pin "11") (pinfunction "V-_11") (pintype "power_in"))
      (node (ref "IC5") (pin "12") (pinfunction "+IN_12") (pintype "input"))
      (node (ref "IC5") (pin "3") (pinfunction "+IN_3") (pintype "input"))
      (node (ref "IC5") (pin "5") (pinfunction "+IN_5") (pintype "input"))
      (node (ref "IC6") (pin "10") (pinfunction "+IN_10") (pintype "input"))
      (node (ref "IC6") (pin "12") (pinfunction "+IN_12") (pintype "input"))
      (node (ref "IC6") (pin "3") (pinfunction "+IN_3") (pintype "input"))
      (node (ref "IC6") (pin "5") (pinfunction "+IN_5") (pintype "input"))
      (node (ref "IC7") (pin "1") (pinfunction "GND_1") (pintype "passive"))
      (node (ref "IC8") (pin "2") (pinfunction "C_2") (pintype "input"))
      (node (ref "Q1") (pin "3") (pinfunction "E_3") (pintype "passive"))
      (node (ref "Q2") (pin "3") (pinfunction "E_3") (pintype "passive"))
      (node (ref "R56") (pin "1") (pinfunction "1_1") (pintype "passive"))
      (node (ref "R60") (pin "1") (pinfunction "1_1") (pintype "passive"))
      (node (ref "U1") (pin "20") (pinfunction "AGND_20") (pintype "bidirectional"))
      (node (ref "U1") (pin "40") (pinfunction "GND_40") (pintype "bidirectional"))
    )
    (net (code "28") (name "Net-(0-3)") (class "Default")
      (node (ref "0") (pin "1") (pinfunction "3_1") (pintype "passive"))
      (node (ref "U1") (pin "1") (pinfunction "GPIO1(USB_HS_ID)_1") (pintype "bidirectional"))
    )
    (net (code "29") (name "Net-(1_SD_D3-3)") (class "Default")
      (node (ref "1_SD_D3") (pin "1") (pinfunction "3_1") (pintype "passive"))
      (node (ref "U1") (pin "2") (pinfunction "GPIO2(SDMMC1_D3)_2") (pintype "bidirectional"))
    )
    (net (code "30") (name "Net-(2_SD_D2-3)") (class "Default")
      (node (ref "2_SD_D2") (pin "1") (pinfunction "3_1") (pintype "passive"))
      (node (ref "U1") (pin "3") (pinfunction "GPIO3(SDMMC1_D2)_3") (pintype "bidirectional"))
    )
    (net (code "31") (name "Net-(3_SD_D1-3)") (class "Default")
      (node (ref "3_SD_D1") (pin "1") (pinfunction "3_1") (pintype "passive"))
      (node (ref "U1") (pin "4") (pinfunction "GPIO4(SDMMC1_D1)_4") (pintype "bidirectional"))
    )
    (net (code "32") (name "Net-(4_SD_D0-3)") (class "Default")
      (node (ref "4_SD_D0") (pin "1") (pinfunction "3_1") (pintype "passive"))
      (node (ref "U1") (pin "5") (pinfunction "GPIO5(SDMMC1_D0)_5") (pintype "bidirectional"))
    )
    (net (code "33") (name "Net-(5_SD_CMD-3)") (class "Default")
      (node (ref "5_SD_CMD") (pin "1") (pinfunction "3_1") (pintype "passive"))
      (node (ref "U1") (pin "6") (pinfunction "GPIO6(SDMMC1_CMD)_6") (pintype "bidirectional"))
    )
    (net (code "34") (name "Net-(6_SD_CLK-3)") (class "Default")
      (node (ref "6_SD_CLK") (pin "1") (pinfunction "3_1") (pintype "passive"))
      (node (ref "U1") (pin "7") (pinfunction "GPIO7(SDMMC1_CK)_7") (pintype "bidirectional"))
    )
    (net (code "35") (name "Net-(7_CS-3)") (class "Default")
      (node (ref "7_CS") (pin "1") (pinfunction "3_1") (pintype "passive"))
      (node (ref "U1") (pin "8") (pinfunction "GPIO8(SPI1_NSS)_8") (pintype "bidirectional"))
    )
    (net (code "36") (name "Net-(8_SCK-3)") (class "Default")
      (node (ref "8_SCK") (pin "1") (pinfunction "3_1") (pintype "passive"))
      (node (ref "U1") (pin "9") (pinfunction "GPIO9(SPI1_SCK)_9") (pintype "bidirectional"))
    )
    (net (code "37") (name "Net-(9_MISO-3)") (class "Default")
      (node (ref "9_MISO") (pin "1") (pinfunction "3_1") (pintype "passive"))
      (node (ref "U1") (pin "10") (pinfunction "GPIO10(SPI1_MISO)_10") (pintype "bidirectional"))
    )
    (net (code "38") (name "Net-(10_MOSI-3)") (class "Default")
      (node (ref "10_MOSI") (pin "1") (pinfunction "3_1") (pintype "passive"))
      (node (ref "U1") (pin "11") (pinfunction "GPIO11(SPI1_MOSI)_11") (pintype "bidirectional"))
    )
    (net (code "39") (name "Net-(11-3)") (class "Default")
      (node (ref "11") (pin "1") (pinfunction "3_1") (pintype "passive"))
      (node (ref "U1") (pin "12") (pinfunction "GPIO12(I2C1_SCL)_12") (pintype "bidirectional"))
    )
    (net (code "40") (name "Net-(12-3)") (class "Default")
      (node (ref "12") (pin "1") (pinfunction "3_1") (pintype "passive"))
      (node (ref "U1") (pin "13") (pinfunction "GPIO13(I2C1_SDA)_13") (pintype "bidirectional"))
    )
    (net (code "41") (name "Net-(13_TX-3)") (class "Default")
      (node (ref "13_TX") (pin "1") (pinfunction "3_1") (pintype "passive"))
      (node (ref "U1") (pin "14") (pinfunction "GPIO14(USART1_TX)_14") (pintype "bidirectional"))
    )
    (net (code "42") (name "Net-(14_RX-3)") (class "Default")
      (node (ref "14_RX") (pin "1") (pinfunction "3_1") (pintype "passive"))
      (node (ref "U1") (pin "15") (pinfunction "GPIO15(USART1_RX)_15") (pintype "bidirectional"))
    )
    (net (code "43") (name "Net-(AINL1-3)") (class "Default")
      (node (ref "AINL1") (pin "1") (pinfunction "3_1") (pintype "passive"))
      (node (ref "R1") (pin "1") (pinfunction "1_1") (pintype "passive"))
    )
    (net (code "44") (name "Net-(AINL2-3)") (class "Default")
      (node (ref "AINL2") (pin "1") (pinfunction "3_1") (pintype "passive"))
      (node (ref "R6") (pin "1") (pinfunction "1_1") (pintype "passive"))
    )
    (net (code "45") (name "Net-(AINR1-3)") (class "Default")
      (node (ref "AINR1") (pin "1") (pinfunction "3_1") (pintype "passive"))
      (node (ref "R2") (pin "1") (pinfunction "1_1") (pintype "passive"))
    )
    (net (code "46") (name "Net-(AINR2-3)") (class "Default")
      (node (ref "AINR2") (pin "1") (pinfunction "3_1") (pintype "passive"))
      (node (ref "R4") (pin "1") (pinfunction "1_1") (pintype "passive"))
    )
    (net (code "47") (name "Net-(AOUTL1-3)") (class "Default")
      (node (ref "AOUTL1") (pin "1") (pinfunction "3_1") (pintype "passive"))
      (node (ref "R20") (pin "2") (pinfunction "2_2") (pintype "passive"))
    )
    (net (code "48") (name "Net-(AOUTR1-3)") (class "Default")
      (node (ref "AOUTR1") (pin "1") (pinfunction "3_1") (pintype "passive"))
      (node (ref "R19") (pin "2") (pinfunction "2_2") (pintype "passive"))
    )
    (net (code "49") (name "Net-(CV1A-3)") (class "Default")
      (node (ref "CV1A") (pin "1") (pinfunction "3_1") (pintype "passive"))
      (node (ref "R22") (pin "1") (pinfunction "1_1") (pintype "passive"))
    )
    (net (code "50") (name "Net-(CV1B-3)") (class "Default")
      (node (ref "CV1B") (pin "1") (pinfunction "3_1") (pintype "passive"))
      (node (ref "R23") (pin "1") (pinfunction "1_1") (pintype "passive"))
    )
    (net (code "51") (name "Net-(CV2A-3)") (class "Default")
      (node (ref "CV2A") (pin "1") (pinfunction "3_1") (pintype "passive"))
      (node (ref "R27") (pin "1") (pinfunction "1_1") (pintype "passive"))
    )
    (net (code "52") (name "Net-(CV2B-3)") (class "Default")
      (node (ref "CV2B") (pin "1") (pinfunction "3_1") (pintype "passive"))
      (node (ref "R28") (pin "1") (pinfunction "1_1") (pintype "passive"))
    )
    (net (code "53") (name "Net-(CV3A-3)") (class "Default")
      (node (ref "CV3A") (pin "1") (pinfunction "3_1") (pintype "passive"))
      (node (ref "R31") (pin "1") (pinfunction "1_1") (pintype "passive"))
    )
    (net (code "54") (name "Net-(CV3B-3)") (class "Default")
      (node (ref "CV3B") (pin "1") (pinfunction "3_1") (pintype "passive"))
      (node (ref "R32") (pin "1") (pinfunction "1_1") (pintype "passive"))
    )
    (net (code "55") (name "Net-(CV4A-3)") (class "Default")
      (node (ref "CV4A") (pin "1") (pinfunction "3_1") (pintype "passive"))
      (node (ref "R35") (pin "1") (pinfunction "1_1") (pintype "passive"))
    )
    (net (code "56") (name "Net-(CV4B-3)") (class "Default")
      (node (ref "CV4B") (pin "1") (pinfunction "3_1") (pintype "passive"))
      (node (ref "R36") (pin "1") (pinfunction "1_1") (pintype "passive"))
    )
    (net (code "57") (name "Net-(CV5A-3)") (class "Default")
      (node (ref "CV5A") (pin "1") (pinfunction "3_1") (pintype "passive"))
      (node (ref "R39") (pin "1") (pinfunction "1_1") (pintype "passive"))
    )
    (net (code "58") (name "Net-(CV5B-3)") (class "Default")
      (node (ref "CV5B") (pin "1") (pinfunction "3_1") (pintype "passive"))
      (node (ref "R40") (pin "1") (pinfunction "1_1") (pintype "passive"))
    )
    (net (code "59") (name "Net-(CV6A-3)") (class "Default")
      (node (ref "CV6A") (pin "1") (pinfunction "3_1") (pintype "passive"))
      (node (ref "R44") (pin "1") (pinfunction "1_1") (pintype "passive"))
    )
    (net (code "60") (name "Net-(CV6B-3)") (class "Default")
      (node (ref "CV6B") (pin "1") (pinfunction "3_1") (pintype "passive"))
      (node (ref "R45") (pin "1") (pinfunction "1_1") (pintype "passive"))
    )
    (net (code "61") (name "Net-(CV7A-3)") (class "Default")
      (node (ref "CV7A") (pin "1") (pinfunction "3_1") (pintype "passive"))
      (node (ref "R47") (pin "1") (pinfunction "1_1") (pintype "passive"))
    )
    (net (code "62") (name "Net-(CV7B-3)") (class "Default")
      (node (ref "CV7B") (pin "1") (pinfunction "3_1") (pintype "passive"))
      (node (ref "R48") (pin "1") (pinfunction "1_1") (pintype "passive"))
    )
    (net (code "63") (name "Net-(CV8A-3)") (class "Default")
      (node (ref "CV8A") (pin "1") (pinfunction "3_1") (pintype "passive"))
      (node (ref "R51") (pin "1") (pinfunction "1_1") (pintype "passive"))
    )
    (net (code "64") (name "Net-(CV8B-3)") (class "Default")
      (node (ref "CV8B") (pin "1") (pinfunction "3_1") (pintype "passive"))
      (node (ref "R52") (pin "1") (pinfunction "1_1") (pintype "passive"))
    )
    (net (code "65") (name "Net-(CVOUT1-3)") (class "Default")
      (node (ref "CVOUT1") (pin "1") (pinfunction "3_1") (pintype "passive"))
      (node (ref "R63") (pin "2") (pinfunction "2_2") (pintype "passive"))
    )
    (net (code "66") (name "Net-(CVOUT2-3)") (class "Default")
      (node (ref "CVOUT2") (pin "1") (pinfunction "3_1") (pintype "passive"))
      (node (ref "R62") (pin "2") (pinfunction "2_2") (pintype "passive"))
    )
    (net (code "67") (name "Net-(GTIN1-3)") (class "Default")
      (node (ref "GTIN1") (pin "1") (pinfunction "3_1") (pintype "passive"))
      (node (ref "R55") (pin "1") (pinfunction "1_1") (pintype "passive"))
    )
    (net (code "68") (name "Net-(GTIN2-3)") (class "Default")
      (node (ref "GTIN2") (pin "1") (pinfunction "3_1") (pintype "passive"))
      (node (ref "R59") (pin "1") (pinfunction "1_1") (pintype "passive"))
    )
    (net (code "69") (name "Net-(GTOUT-3)") (class "Default")
      (node (ref "GTOUT") (pin "1") (pinfunction "3_1") (pintype "passive"))
      (node (ref "R70") (pin "2") (pinfunction "2_2") (pintype "passive"))
    )
    (net (code "70") (name "Net-(IC1A--IN)") (class "Default")
      (node (ref "C4") (pin "1") (pinfunction "1_1") (pintype "passive"))
      (node (ref "IC1") (pin "2") (pinfunction "-IN_2") (pintype "input"))
      (node (ref "R2") (pin "2") (pinfunction "2_2") (pintype "passive"))
      (node (ref "R3") (pin "1") (pinfunction "1_1") (pintype "passive"))
      (node (ref "R4") (pin "2") (pinfunction "2_2") (pintype "passive"))
    )
    (net (code "71") (name "Net-(IC1A-OUT)") (class "Default")
      (node (ref "C4") (pin "2") (pinfunction "2_2") (pintype "passive"))
      (node (ref "IC1") (pin "1") (pinfunction "OUT_1") (pintype "output"))
      (node (ref "R3") (pin "2") (pinfunction "2_2") (pintype "passive"))
      (node (ref "R9") (pin "1") (pinfunction "1_1") (pintype "passive"))
    )
    (net (code "72") (name "Net-(IC1B--IN)") (class "Default")
      (node (ref "C5") (pin "1") (pinfunction "1_1") (pintype "passive"))
      (node (ref "IC1") (pin "6") (pinfunction "-IN_6") (pintype "input"))
      (node (ref "R1") (pin "2") (pinfunction "2_2") (pintype "passive"))
      (node (ref "R5") (pin "1") (pinfunction "1_1") (pintype "passive"))
      (node (ref "R6") (pin "2") (pinfunction "2_2") (pintype "passive"))
    )
    (net (code "73") (name "Net-(IC1B-OUT)") (class "Default")
      (node (ref "C5") (pin "2") (pinfunction "2_2") (pintype "passive"))
      (node (ref "IC1") (pin "7") (pinfunction "OUT_7") (pintype "output"))
      (node (ref "R10") (pin "1") (pinfunction "1_1") (pintype "passive"))
      (node (ref "R5") (pin "2") (pinfunction "2_2") (pintype "passive"))
    )
    (net (code "74") (name "Net-(IC1C--IN)") (class "Default")
      (node (ref "C12") (pin "1") (pinfunction "1_1") (pintype "passive"))
      (node (ref "IC1") (pin "9") (pinfunction "-IN_9") (pintype "input"))
      (node (ref "R14") (pin "1") (pinfunction "1_1") (pintype "passive"))
      (node (ref "R17") (pin "2") (pinfunction "2_2") (pintype "passive"))
    )
    (net (code "75") (name "Net-(IC1C-OUT)") (class "Default")
      (node (ref "C12") (pin "2") (pinfunction "2_2") (pintype "passive"))
      (node (ref "IC1") (pin "8") (pinfunction "OUT_8") (pintype "output"))
      (node (ref "R14") (pin "2") (pinfunction "2_2") (pintype "passive"))
      (node (ref "R19") (pin "1") (pinfunction "1_1") (pintype "passive"))
    )
    (net (code "76") (name "Net-(IC1D--IN)") (class "Default")
      (node (ref "C13") (pin "1") (pinfunction "1_1") (pintype "passive"))
      (node (ref "IC1") (pin "13") (pinfunction "-IN_13") (pintype "input"))
      (node (ref "R16") (pin "1") (pinfunction "1_1") (pintype "passive"))
      (node (ref "R18") (pin "2") (pinfunction "2_2") (pintype "passive"))
    )
    (net (code "77") (name "Net-(IC1D-OUT)") (class "Default")
      (node (ref "C13") (pin "2") (pinfunction "2_2") (pintype "passive"))
      (node (ref "IC1") (pin "14") (pinfunction "OUT_14") (pintype "output"))
      (node (ref "R16") (pin "2") (pinfunction "2_2") (pintype "passive"))
      (node (ref "R20") (pin "1") (pinfunction "1_1") (pintype "passive"))
    )
    (net (code "78") (name "Net-(IC4A--IN)") (class "Default")
      (node (ref "C16") (pin "1") (pinfunction "1_1") (pintype "passive"))
      (node (ref "IC4") (pin "2") (pinfunction "-IN_2") (pintype "input"))
      (node (ref "R21") (pin "1") (pinfunction "1_1") (pintype "passive"))
      (node (ref "R22") (pin "2") (pinfunction "2_2") (pintype "passive"))
      (node (ref "R23") (pin "2") (pinfunction "2_2") (pintype "passive"))
      (node (ref "R24") (pin "2") (pinfunction "2_2") (pintype "passive"))
    )
    (net (code "79") (name "Net-(IC4B--IN)") (class "Default")
      (node (ref "C17") (pin "1") (pinfunction "1_1") (pintype "passive"))
      (node (ref "IC4") (pin "6") (pinfunction "-IN_6") (pintype "input"))
      (node (ref "R25") (pin "1") (pinfunction "1_1") (pintype "passive"))
      (node (ref "R26") (pin "2") (pinfunction "2_2") (pintype "passive"))
      (node (ref "R27") (pin "2") (pinfunction "2_2") (pintype "passive"))
      (node (ref "R28") (pin "2") (pinfunction "2_2") (pintype "passive"))
    )
    (net (code "80") (name "Net-(IC4C--IN)") (class "Default")
      (node (ref "C20") (pin "1") (pinfunction "1_1") (pintype "passive"))
      (node (ref "IC4") (pin "9") (pinfunction "-IN_9") (pintype "input"))
      (node (ref "R30") (pin "1") (pinfunction "1_1") (pintype "passive"))
      (node (ref "R31") (pin "2") (pinfunction "2_2") (pintype "passive"))
      (node (ref "R32") (pin "2") (pinfunction "2_2") (pintype "passive"))
      (node (ref "R33") (pin "2") (pinfunction "2_2") (pintype "passive"))
    )
    (net (code "81") (name "Net-(IC4D--IN)") (class "Default")
      (node (ref "C21") (pin "1") (pinfunction "1_1") (pintype "passive"))
      (node (ref "IC4") (pin "13") (pinfunction "-IN_13") (pintype "input"))
      (node (ref "R34") (pin "1") (pinfunction "1_1") (pintype "passive"))
      (node (ref "R35") (pin "2") (pinfunction "2_2") (pintype "passive"))
      (node (ref "R36") (pin "2") (pinfunction "2_2") (pintype "passive"))
      (node (ref "R37") (pin "2") (pinfunction "2_2") (pintype "passive"))
    )
    (net (code "82") (name "Net-(IC5A--IN)") (class "Default")
      (node (ref "C22") (pin "1") (pinfunction "1_1") (pintype "passive"))
      (node (ref "IC5") (pin "2") (pinfunction "-IN_2") (pintype "input"))
      (node (ref "R38") (pin "1") (pinfunction "1_1") (pintype "passive"))
      (node (ref "R39") (pin "2") (pinfunction "2_2") (pintype "passive"))
      (node (ref "R40") (pin "2") (pinfunction "2_2") (pintype "passive"))
      (node (ref "R41") (pin "2") (pinfunction "2_2") (pintype "passive"))
    )
    (net (code "83") (name "Net-(IC5B--IN)") (class "Default")
      (node (ref "C23") (pin "1") (pinfunction "1_1") (pintype "passive"))
      (node (ref "IC5") (pin "6") (pinfunction "-IN_6") (pintype "input"))
      (node (ref "R42") (pin "1") (pinfunction "1_1") (pintype "passive"))
      (node (ref "R43") (pin "2") (pinfunction "2_2") (pintype "passive"))
      (node (ref "R44") (pin "2") (pinfunction "2_2") (pintype "passive"))
      (node (ref "R45") (pin "2") (pinfunction "2_2") (pintype "passive"))
    )
    (net (code "84") (name "Net-(IC5C--IN)") (class "Default")
      (node (ref "C24") (pin "1") (pinfunction "1_1") (pintype "passive"))
      (node (ref "IC5") (pin "9") (pinfunction "-IN_9") (pintype "input"))
      (node (ref "R46") (pin "1") (pinfunction "1_1") (pintype "passive"))
      (node (ref "R47") (pin "2") (pinfunction "2_2") (pintype "passive"))
      (node (ref "R48") (pin "2") (pinfunction "2_2") (pintype "passive"))
      (node (ref "R49") (pin "2") (pinfunction "2_2") (pintype "passive"))
    )
    (net (code "85") (name "Net-(IC5D--IN)") (class "Default")
      (node (ref "C25") (pin "1") (pinfunction "1_1") (pintype "passive"))
      (node (ref "IC5") (pin "13") (pinfunction "-IN_13") (pintype "input"))
      (node (ref "R50") (pin "1") (pinfunction "1_1") (pintype "passive"))
      (node (ref "R51") (pin "2") (pinfunction "2_2") (pintype "passive"))
      (node (ref "R52") (pin "2") (pinfunction "2_2") (pintype "passive"))
      (node (ref "R53") (pin "2") (pinfunction "2_2") (pintype "passive"))
    )
    (net (code "86") (name "Net-(IC6A--IN)") (class "Default")
      (node (ref "IC6") (pin "2") (pinfunction "-IN_2") (pintype "input"))
      (node (ref "R29") (pin "2") (pinfunction "2_2") (pintype "passive"))
      (node (ref "R65") (pin "1") (pinfunction "1_1") (pintype "passive"))
      (node (ref "R68") (pin "2") (pinfunction "2_2") (pintype "passive"))
    )
    (net (code "87") (name "Net-(IC6A-OUT)") (class "Default")
      (node (ref "IC6") (pin "1") (pinfunction "OUT_1") (pintype "output"))
      (node (ref "R63") (pin "1") (pinfunction "1_1") (pintype "passive"))
      (node (ref "R65") (pin "2") (pinfunction "2_2") (pintype "passive"))
    )
    (net (code "88") (name "Net-(IC6B--IN)") (class "Default")
      (node (ref "IC6") (pin "6") (pinfunction "-IN_6") (pintype "input"))
      (node (ref "R66") (pin "1") (pinfunction "1_1") (pintype "passive"))
      (node (ref "R73") (pin "2") (pinfunction "2_2") (pintype "passive"))
    )
    (net (code "89") (name "Net-(IC6B-OUT)") (class "Default")
      (node (ref "IC6") (pin "7") (pinfunction "OUT_7") (pintype "output"))
      (node (ref "R66") (pin "2") (pinfunction "2_2") (pintype "passive"))
      (node (ref "R71") (pin "1") (pinfunction "1_1") (pintype "passive"))
    )
    (net (code "90") (name "Net-(IC6C--IN)") (class "Default")
      (node (ref "IC6") (pin "9") (pinfunction "-IN_9") (pintype "input"))
      (node (ref "R64") (pin "1") (pinfunction "1_1") (pintype "passive"))
      (node (ref "R71") (pin "2") (pinfunction "2_2") (pintype "passive"))
    )
    (net (code "91") (name "Net-(IC6C-OUT)") (class "Default")
      (node (ref "IC6") (pin "8") (pinfunction "OUT_8") (pintype "output"))
      (node (ref "R64") (pin "2") (pinfunction "2_2") (pintype "passive"))
      (node (ref "R70") (pin "1") (pinfunction "1_1") (pintype "passive"))
    )
    (net (code "92") (name "Net-(IC6D--IN)") (class "Default")
      (node (ref "IC6") (pin "13") (pinfunction "-IN_13") (pintype "input"))
      (node (ref "R67") (pin "1") (pinfunction "1_1") (pintype "passive"))
      (node (ref "R69") (pin "2") (pinfunction "2_2") (pintype "passive"))
      (node (ref "R72") (pin "2") (pinfunction "2_2") (pintype "passive"))
    )
    (net (code "93") (name "Net-(IC6D-OUT)") (class "Default")
      (node (ref "IC6") (pin "14") (pinfunction "OUT_14") (pintype "output"))
      (node (ref "R62") (pin "1") (pinfunction "1_1") (pintype "passive"))
      (node (ref "R67") (pin "2") (pinfunction "2_2") (pintype "passive"))
    )
    (net (code "94") (name "Net-(Q1-B)") (class "Default")
      (node (ref "Q1") (pin "2") (pinfunction "B_2") (pintype "passive"))
      (node (ref "R55") (pin "2") (pinfunction "2_2") (pintype "passive"))
      (node (ref "R56") (pin "2") (pinfunction "2_2") (pintype "passive"))
    )
    (net (code "95") (name "Net-(Q1-C)") (class "Default")
      (node (ref "Q1") (pin "1") (pinfunction "C_1") (pintype "passive"))
      (node (ref "R54") (pin "1") (pinfunction "1_1") (pintype "passive"))
      (node (ref "R57") (pin "1") (pinfunction "1_1") (pintype "passive"))
    )
    (net (code "96") (name "Net-(Q2-B)") (class "Default")
      (node (ref "Q2") (pin "2") (pinfunction "B_2") (pintype "passive"))
      (node (ref "R59") (pin "2") (pinfunction "2_2") (pintype "passive"))
      (node (ref "R60") (pin "2") (pinfunction "2_2") (pintype "passive"))
    )
    (net (code "97") (name "Net-(Q2-C)") (class "Default")
      (node (ref "Q2") (pin "1") (pinfunction "C_1") (pintype "passive"))
      (node (ref "R58") (pin "1") (pinfunction "1_1") (pintype "passive"))
      (node (ref "R61") (pin "1") (pinfunction "1_1") (pintype "passive"))
    )
  )
)
